# button_brick.net
KiCad netlist of a schematic drawn in EAGLE
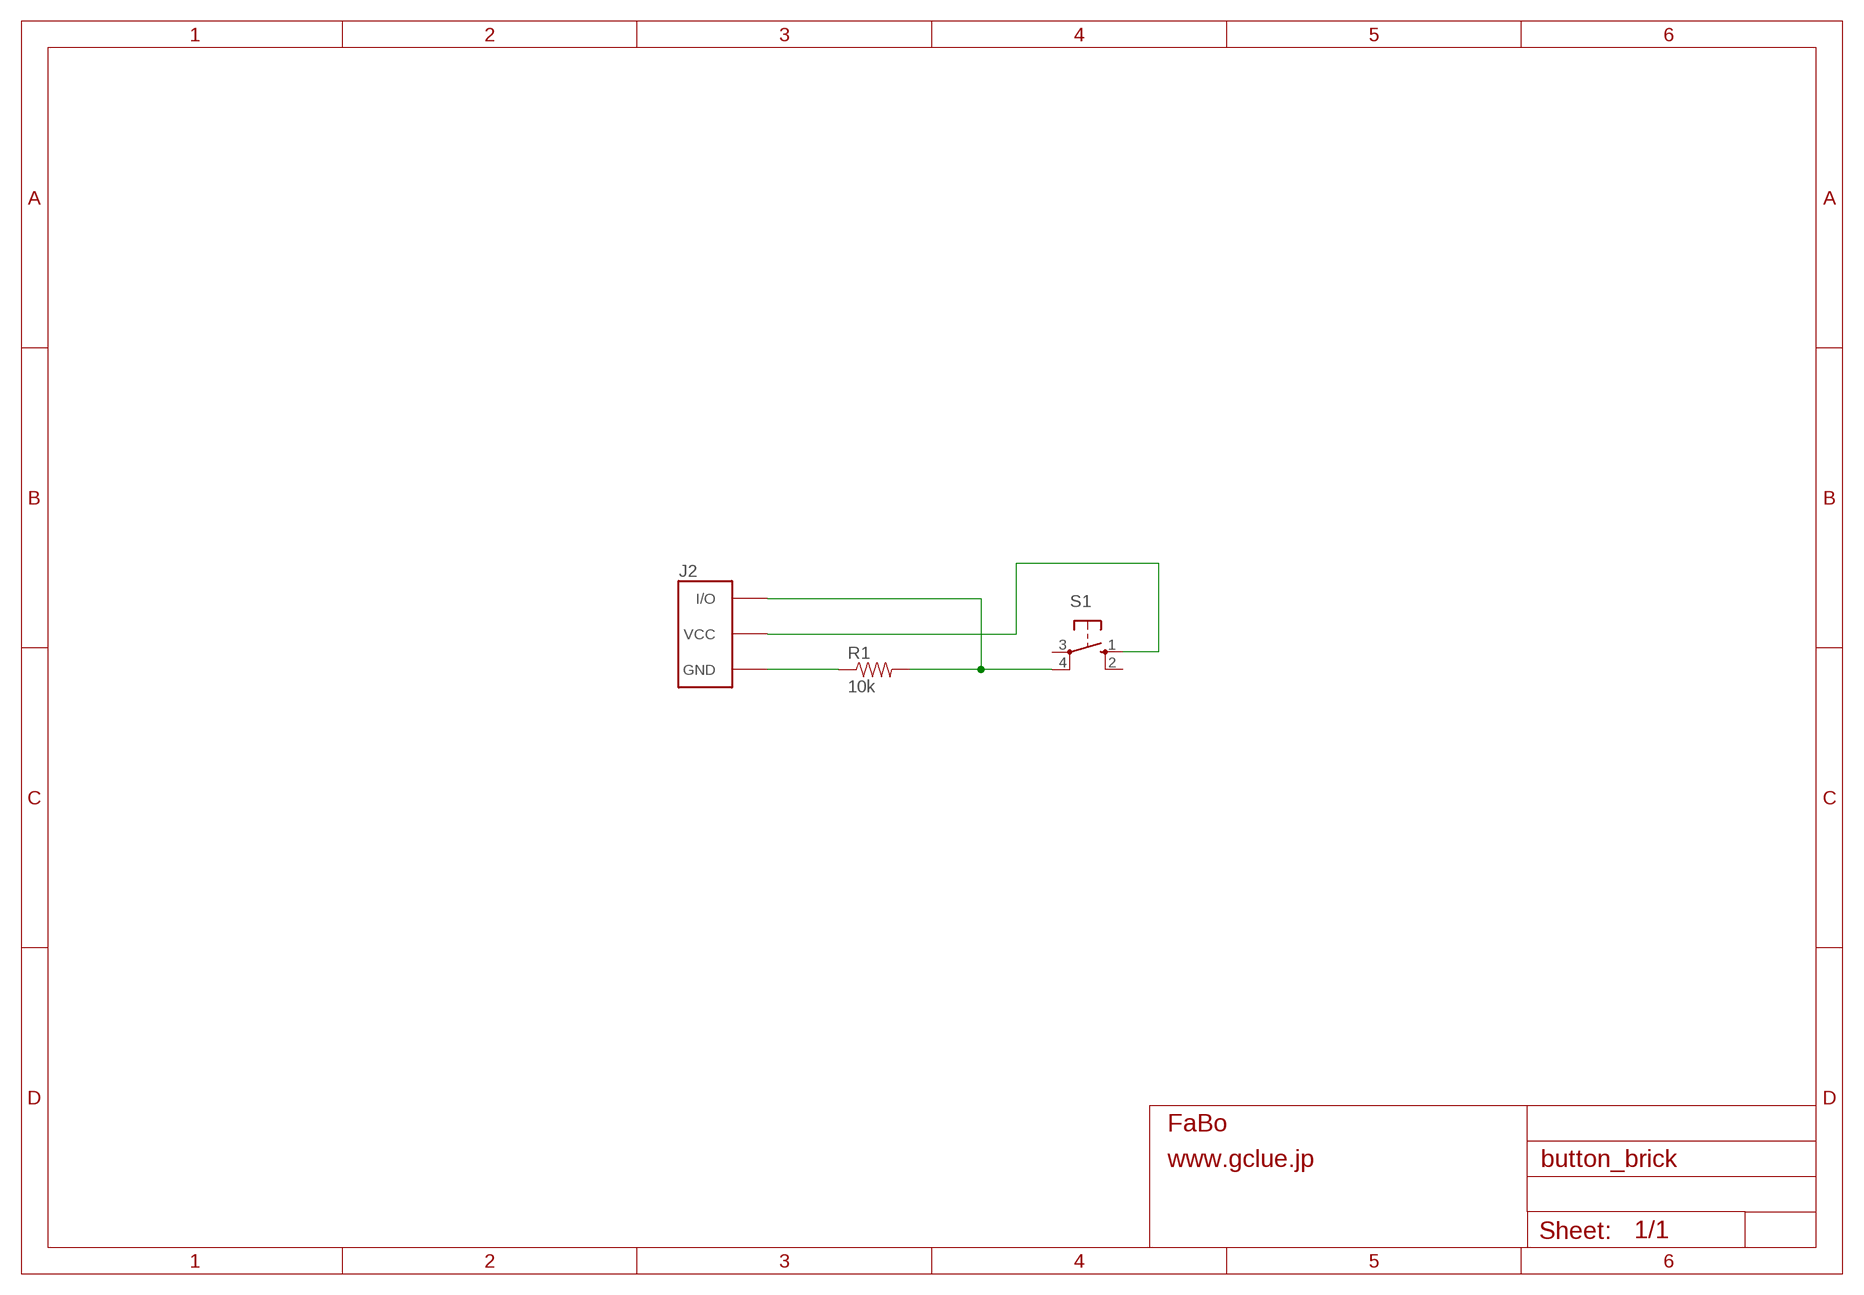
[diagram p0: schematic, sheet 1]

(export (version "E")
  (design (tool "Eeschema 10.0.6"))
  (components
    (comp (ref "J2")
      (value "BRICK_3PIN")
      (footprint "eagle-import:BRICK_3PIN")
      (libsource (lib "eagle-import") (part "BRICK_3PIN"))
    )
    (comp (ref "R1")
      (value "10k")
      (footprint "eagle-import:AXIAL-0.4")
      (libsource (lib "eagle-import") (part "RESISTORPTH-1/4W"))
    )
    (comp (ref "S1")
      (value "Button")
      (footprint "eagle-import:B3F-10XX")
      (fields (field (name "MPN") "B3F-1000"))
      (libsource (lib "eagle-import") (part "10-XX"))
    )
  )
  (nets
    (net (code "1") (name "Net-(J2-I{slash}O)") (class "Default")
      (node (ref "J2") (pin "IN/OUT") (pinfunction "I/O_IN/OUT") (pintype "bidirectional"))
      (node (ref "R1") (pin "P$2") (pinfunction "2_P$2") (pintype "passive"))
      (node (ref "S1") (pin "4") (pinfunction "P1_4") (pintype "passive"))
    )
    (net (code "2") (name "Net-(R1-1)") (class "Default")
      (node (ref "J2") (pin "GND") (pinfunction "GND_GND") (pintype "bidirectional"))
      (node (ref "R1") (pin "P$1") (pinfunction "1_P$1") (pintype "passive"))
    )
    (net (code "3") (name "Net-(S1-S)") (class "Default")
      (node (ref "J2") (pin "VCC") (pinfunction "VCC_VCC") (pintype "bidirectional"))
      (node (ref "S1") (pin "1") (pinfunction "S_1") (pintype "passive"))
    )
    (net (code "4") (name "unconnected-(S1-P-Pad3)") (class "Default")
      (node (ref "S1") (pin "3") (pinfunction "P_3") (pintype "passive"))
    )
    (net (code "5") (name "unconnected-(S1-S1-Pad2)") (class "Default")
      (node (ref "S1") (pin "2") (pinfunction "S1_2") (pintype "passive"))
    )
  )
)
